# ViDieuKhienSTM32F103C8T6.net
KiCad netlist of a schematic drawn in Altium Designer
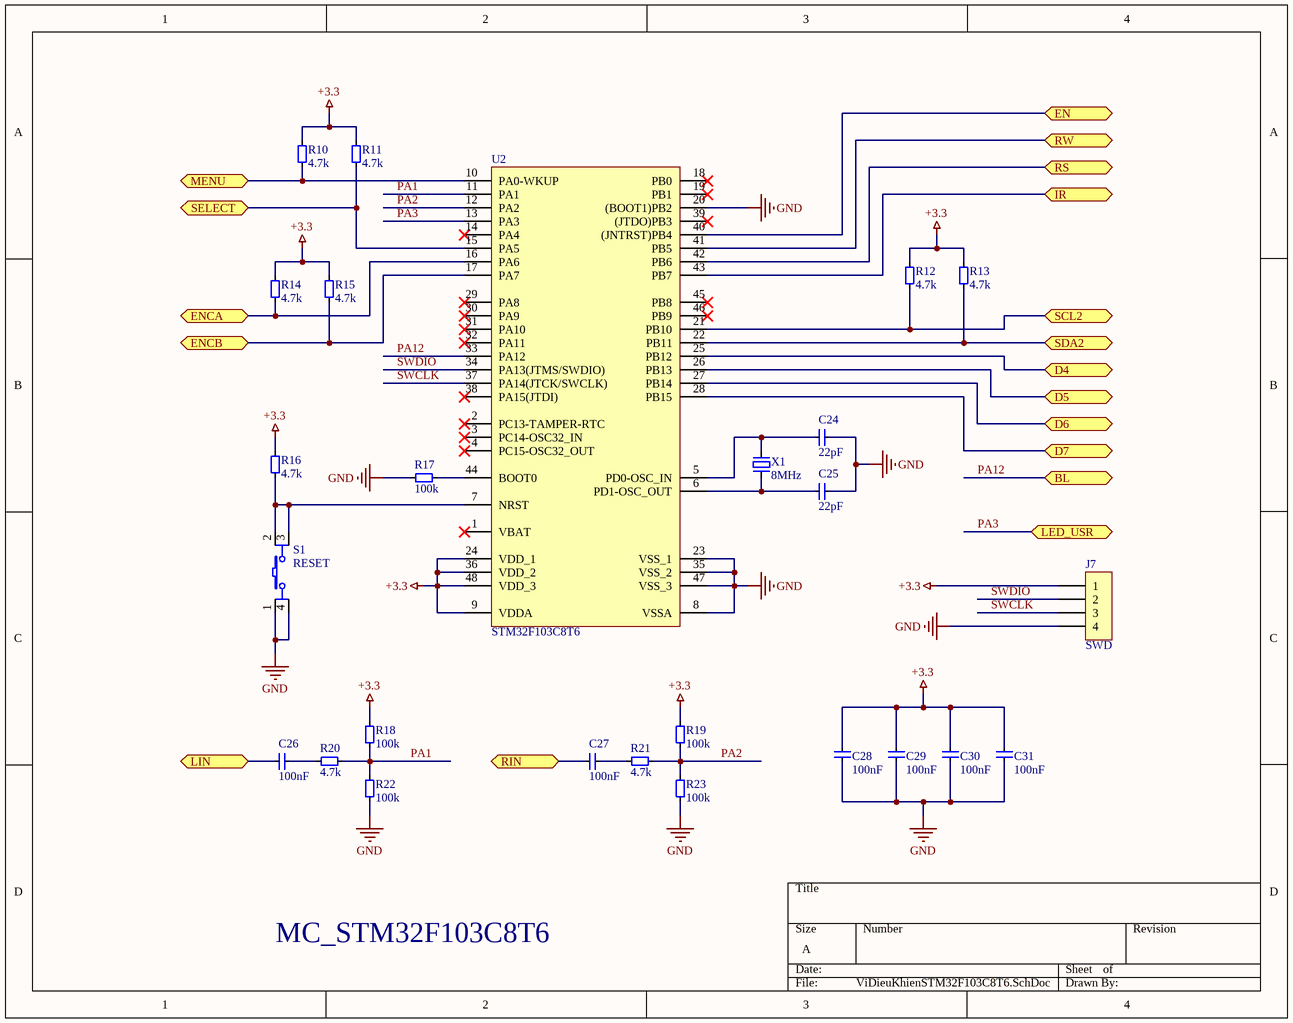
[diagram p0: ViDieuKhienSTM32F103C8T6.SchDoc]

(export (version "E")
  (design (tool "Eeschema 10.0.6"))
  (components
    (comp (ref "C24")
      (value "22pF")
      (footprint "C-0805")
      (description "Cac Loai Tu Khong Phan Cuc")
      (libsource (lib "phatvu1294_Lib") (part "CAP"))
    )
    (comp (ref "C25")
      (value "22pF")
      (footprint "C-0805")
      (description "Cac Loai Tu Khong Phan Cuc")
      (libsource (lib "phatvu1294_Lib") (part "CAP"))
    )
    (comp (ref "C26")
      (value "100nF")
      (footprint "C-0805")
      (description "Cac Loai Tu Khong Phan Cuc")
      (libsource (lib "phatvu1294_Lib") (part "CAP"))
    )
    (comp (ref "C27")
      (value "100nF")
      (footprint "C-0805")
      (description "Cac Loai Tu Khong Phan Cuc")
      (libsource (lib "phatvu1294_Lib") (part "CAP"))
    )
    (comp (ref "C28")
      (value "100nF")
      (footprint "C-0805")
      (description "Cac Loai Tu Khong Phan Cuc")
      (libsource (lib "phatvu1294_Lib") (part "CAP"))
    )
    (comp (ref "C29")
      (value "100nF")
      (footprint "C-0805")
      (description "Cac Loai Tu Khong Phan Cuc")
      (libsource (lib "phatvu1294_Lib") (part "CAP"))
    )
    (comp (ref "C30")
      (value "100nF")
      (footprint "C-0805")
      (description "Cac Loai Tu Khong Phan Cuc")
      (libsource (lib "phatvu1294_Lib") (part "CAP"))
    )
    (comp (ref "C31")
      (value "100nF")
      (footprint "C-0805")
      (description "Cac Loai Tu Khong Phan Cuc")
      (libsource (lib "phatvu1294_Lib") (part "CAP"))
    )
    (comp (ref "J7")
      (value "SWD")
      (footprint "JP1X4M-2.54")
      (description "Jump Don 4 Chan 2.54mm")
      (libsource (lib "phatvu1294_Lib") (part "JP1X4-2.54"))
    )
    (comp (ref "R10")
      (value "4.7k")
      (footprint "R-0805")
      (description "Cac Loai Dien Tro")
      (libsource (lib "phatvu1294_Lib") (part "RES"))
    )
    (comp (ref "R11")
      (value "4.7k")
      (footprint "R-0805")
      (description "Cac Loai Dien Tro")
      (libsource (lib "phatvu1294_Lib") (part "RES"))
    )
    (comp (ref "R12")
      (value "4.7k")
      (footprint "R-0805")
      (description "Cac Loai Dien Tro")
      (libsource (lib "phatvu1294_Lib") (part "RES"))
    )
    (comp (ref "R13")
      (value "4.7k")
      (footprint "R-0805")
      (description "Cac Loai Dien Tro")
      (libsource (lib "phatvu1294_Lib") (part "RES"))
    )
    (comp (ref "R14")
      (value "4.7k")
      (footprint "R-0805")
      (description "Cac Loai Dien Tro")
      (libsource (lib "phatvu1294_Lib") (part "RES"))
    )
    (comp (ref "R15")
      (value "4.7k")
      (footprint "R-0805")
      (description "Cac Loai Dien Tro")
      (libsource (lib "phatvu1294_Lib") (part "RES"))
    )
    (comp (ref "R16")
      (value "4.7k")
      (footprint "R-0805")
      (description "Cac Loai Dien Tro")
      (libsource (lib "phatvu1294_Lib") (part "RES"))
    )
    (comp (ref "R17")
      (value "100k")
      (footprint "R-0805")
      (description "Cac Loai Dien Tro")
      (libsource (lib "phatvu1294_Lib") (part "RES"))
    )
    (comp (ref "R18")
      (value "100k")
      (footprint "R-0805")
      (description "Cac Loai Dien Tro")
      (libsource (lib "phatvu1294_Lib") (part "RES"))
    )
    (comp (ref "R19")
      (value "100k")
      (footprint "R-0805")
      (description "Cac Loai Dien Tro")
      (libsource (lib "phatvu1294_Lib") (part "RES"))
    )
    (comp (ref "R20")
      (value "4.7k")
      (footprint "R-0805")
      (description "Cac Loai Dien Tro")
      (libsource (lib "phatvu1294_Lib") (part "RES"))
    )
    (comp (ref "R21")
      (value "4.7k")
      (footprint "R-0805")
      (description "Cac Loai Dien Tro")
      (libsource (lib "phatvu1294_Lib") (part "RES"))
    )
    (comp (ref "R22")
      (value "100k")
      (footprint "R-0805")
      (description "Cac Loai Dien Tro")
      (libsource (lib "phatvu1294_Lib") (part "RES"))
    )
    (comp (ref "R23")
      (value "100k")
      (footprint "R-0805")
      (description "Cac Loai Dien Tro")
      (libsource (lib "phatvu1294_Lib") (part "RES"))
    )
    (comp (ref "S1")
      (value "RESET")
      (footprint "SW4P-DIP-6X6MM")
      (description "Nut Nhan 4 Chan 6X6MM")
      (libsource (lib "phatvu1294_Lib") (part "SW4P-DIP-6X6MM"))
    )
    (comp (ref "U2")
      (value "STM32F103C8T6")
      (footprint "LQFP48-0.5-7X7MM")
      (description "VDK 32-Bit ARM Cortex-M3")
      (libsource (lib "phatvu1294_Lib") (part "STM32F103C8T6"))
    )
    (comp (ref "X1")
      (value "8MHz")
      (footprint "XTAL-HC49US")
      (description "Thach Anh 2 Chan HC49")
      (libsource (lib "phatvu1294_Lib") (part "XTAL-HC49"))
    )
  )
  (nets
    (net (code "1") (name "+3.3") (class "Default")
      (node (ref "C28") (pin "1") (pinfunction "1_1") (pintype "passive"))
      (node (ref "C29") (pin "1") (pinfunction "1_1") (pintype "passive"))
      (node (ref "C30") (pin "1") (pinfunction "1_1") (pintype "passive"))
      (node (ref "C31") (pin "1") (pinfunction "1_1") (pintype "passive"))
      (node (ref "J7") (pin "1") (pinfunction "1_1") (pintype "passive"))
      (node (ref "R10") (pin "2") (pinfunction "2_2") (pintype "passive"))
      (node (ref "R11") (pin "2") (pinfunction "2_2") (pintype "passive"))
      (node (ref "R12") (pin "2") (pinfunction "2_2") (pintype "passive"))
      (node (ref "R13") (pin "2") (pinfunction "2_2") (pintype "passive"))
      (node (ref "R14") (pin "2") (pinfunction "2_2") (pintype "passive"))
      (node (ref "R15") (pin "2") (pinfunction "2_2") (pintype "passive"))
      (node (ref "R16") (pin "2") (pinfunction "2_2") (pintype "passive"))
      (node (ref "R18") (pin "2") (pinfunction "2_2") (pintype "passive"))
      (node (ref "R19") (pin "2") (pinfunction "2_2") (pintype "passive"))
      (node (ref "U2") (pin "24") (pinfunction "VDD_1_24") (pintype "power_in"))
      (node (ref "U2") (pin "36") (pinfunction "VDD_2_36") (pintype "power_in"))
      (node (ref "U2") (pin "48") (pinfunction "VDD_3_48") (pintype "power_in"))
      (node (ref "U2") (pin "9") (pinfunction "VDDA_9") (pintype "power_in"))
    )
    (net (code "2") (name "/D4") (class "Default")
      (node (ref "U2") (pin "25") (pinfunction "PB12_25") (pintype "passive"))
    )
    (net (code "3") (name "/D5") (class "Default")
      (node (ref "U2") (pin "26") (pinfunction "PB13_26") (pintype "passive"))
    )
    (net (code "4") (name "/D6") (class "Default")
      (node (ref "U2") (pin "27") (pinfunction "PB14_27") (pintype "passive"))
    )
    (net (code "5") (name "/D7") (class "Default")
      (node (ref "U2") (pin "28") (pinfunction "PB15_28") (pintype "passive"))
    )
    (net (code "6") (name "/EN") (class "Default")
      (node (ref "U2") (pin "40") (pinfunction "(JNTRST)PB4_40") (pintype "passive"))
    )
    (net (code "7") (name "/ENCA") (class "Default")
      (node (ref "R14") (pin "1") (pinfunction "1_1") (pintype "passive"))
      (node (ref "U2") (pin "16") (pinfunction "PA6_16") (pintype "passive"))
    )
    (net (code "8") (name "/ENCB") (class "Default")
      (node (ref "R15") (pin "1") (pinfunction "1_1") (pintype "passive"))
      (node (ref "U2") (pin "17") (pinfunction "PA7_17") (pintype "passive"))
    )
    (net (code "9") (name "/IR") (class "Default")
      (node (ref "U2") (pin "43") (pinfunction "PB7_43") (pintype "passive"))
    )
    (net (code "10") (name "/LIN") (class "Default")
      (node (ref "C26") (pin "2") (pinfunction "2_2") (pintype "passive"))
    )
    (net (code "11") (name "/MENU") (class "Default")
      (node (ref "R10") (pin "1") (pinfunction "1_1") (pintype "passive"))
      (node (ref "U2") (pin "10") (pinfunction "PA0-WKUP_10") (pintype "passive"))
    )
    (net (code "12") (name "/PA1") (class "Default")
      (node (ref "R18") (pin "1") (pinfunction "1_1") (pintype "passive"))
      (node (ref "R20") (pin "1") (pinfunction "1_1") (pintype "passive"))
      (node (ref "R22") (pin "2") (pinfunction "2_2") (pintype "passive"))
      (node (ref "U2") (pin "11") (pinfunction "PA1_11") (pintype "passive"))
    )
    (net (code "13") (name "/PA2") (class "Default")
      (node (ref "R19") (pin "1") (pinfunction "1_1") (pintype "passive"))
      (node (ref "R21") (pin "1") (pinfunction "1_1") (pintype "passive"))
      (node (ref "R23") (pin "2") (pinfunction "2_2") (pintype "passive"))
      (node (ref "U2") (pin "12") (pinfunction "PA2_12") (pintype "passive"))
    )
    (net (code "14") (name "/PA3") (class "Default")
      (node (ref "U2") (pin "13") (pinfunction "PA3_13") (pintype "passive"))
    )
    (net (code "15") (name "/PA12") (class "Default")
      (node (ref "U2") (pin "33") (pinfunction "PA12_33") (pintype "passive"))
    )
    (net (code "16") (name "/RIN") (class "Default")
      (node (ref "C27") (pin "2") (pinfunction "2_2") (pintype "passive"))
    )
    (net (code "17") (name "/RS") (class "Default")
      (node (ref "U2") (pin "42") (pinfunction "PB6_42") (pintype "passive"))
    )
    (net (code "18") (name "/RW") (class "Default")
      (node (ref "U2") (pin "41") (pinfunction "PB5_41") (pintype "passive"))
    )
    (net (code "19") (name "/SCL2") (class "Default")
      (node (ref "R12") (pin "1") (pinfunction "1_1") (pintype "passive"))
      (node (ref "U2") (pin "21") (pinfunction "PB10_21") (pintype "passive"))
    )
    (net (code "20") (name "/SDA2") (class "Default")
      (node (ref "R13") (pin "1") (pinfunction "1_1") (pintype "passive"))
      (node (ref "U2") (pin "22") (pinfunction "PB11_22") (pintype "passive"))
    )
    (net (code "21") (name "/SELECT") (class "Default")
      (node (ref "R11") (pin "1") (pinfunction "1_1") (pintype "passive"))
      (node (ref "U2") (pin "15") (pinfunction "PA5_15") (pintype "passive"))
    )
    (net (code "22") (name "/SWCLK") (class "Default")
      (node (ref "J7") (pin "3") (pinfunction "3_3") (pintype "passive"))
      (node (ref "U2") (pin "37") (pinfunction "PA14(JTCK/SWCLK)_37") (pintype "passive"))
    )
    (net (code "23") (name "/SWDIO") (class "Default")
      (node (ref "J7") (pin "2") (pinfunction "2_2") (pintype "passive"))
      (node (ref "U2") (pin "34") (pinfunction "PA13(JTMS/SWDIO)_34") (pintype "passive"))
    )
    (net (code "24") (name "GND") (class "Default")
      (node (ref "C24") (pin "1") (pinfunction "1_1") (pintype "passive"))
      (node (ref "C25") (pin "1") (pinfunction "1_1") (pintype "passive"))
      (node (ref "C28") (pin "2") (pinfunction "2_2") (pintype "passive"))
      (node (ref "C29") (pin "2") (pinfunction "2_2") (pintype "passive"))
      (node (ref "C30") (pin "2") (pinfunction "2_2") (pintype "passive"))
      (node (ref "C31") (pin "2") (pinfunction "2_2") (pintype "passive"))
      (node (ref "J7") (pin "4") (pinfunction "4_4") (pintype "passive"))
      (node (ref "R17") (pin "1") (pinfunction "1_1") (pintype "passive"))
      (node (ref "R22") (pin "1") (pinfunction "1_1") (pintype "passive"))
      (node (ref "R23") (pin "1") (pinfunction "1_1") (pintype "passive"))
      (node (ref "S1") (pin "1") (pinfunction "1_1") (pintype "passive"))
      (node (ref "S1") (pin "4") (pinfunction "4_4") (pintype "passive"))
      (node (ref "U2") (pin "20") (pinfunction "(BOOT1)PB2_20") (pintype "passive"))
      (node (ref "U2") (pin "23") (pinfunction "VSS_1_23") (pintype "power_in"))
      (node (ref "U2") (pin "35") (pinfunction "VSS_2_35") (pintype "power_in"))
      (node (ref "U2") (pin "47") (pinfunction "VSS_3_47") (pintype "power_in"))
      (node (ref "U2") (pin "8") (pinfunction "VSSA_8") (pintype "power_in"))
    )
    (net (code "25") (name "Net-(C26-Pad1)") (class "Default")
      (node (ref "C26") (pin "1") (pinfunction "1_1") (pintype "passive"))
      (node (ref "R20") (pin "2") (pinfunction "2_2") (pintype "passive"))
    )
    (net (code "26") (name "Net-(C27-Pad1)") (class "Default")
      (node (ref "C27") (pin "1") (pinfunction "1_1") (pintype "passive"))
      (node (ref "R21") (pin "2") (pinfunction "2_2") (pintype "passive"))
    )
    (net (code "27") (name "Net-(U2-BOOT0)") (class "Default")
      (node (ref "R17") (pin "2") (pinfunction "2_2") (pintype "passive"))
      (node (ref "U2") (pin "44") (pinfunction "BOOT0_44") (pintype "passive"))
    )
    (net (code "28") (name "Net-(U2-NRST)") (class "Default")
      (node (ref "R16") (pin "1") (pinfunction "1_1") (pintype "passive"))
      (node (ref "S1") (pin "2") (pinfunction "2_2") (pintype "passive"))
      (node (ref "S1") (pin "3") (pinfunction "3_3") (pintype "passive"))
      (node (ref "U2") (pin "7") (pinfunction "NRST_7") (pintype "passive"))
    )
    (net (code "29") (name "Net-(U2-PD0-OSC_IN)") (class "Default")
      (node (ref "C24") (pin "2") (pinfunction "2_2") (pintype "passive"))
      (node (ref "U2") (pin "5") (pinfunction "PD0-OSC_IN_5") (pintype "passive"))
      (node (ref "X1") (pin "1") (pinfunction "1_1") (pintype "passive"))
    )
    (net (code "30") (name "Net-(U2-PD1-OSC_OUT)") (class "Default")
      (node (ref "C25") (pin "2") (pinfunction "2_2") (pintype "passive"))
      (node (ref "U2") (pin "6") (pinfunction "PD1-OSC_OUT_6") (pintype "passive"))
      (node (ref "X1") (pin "2") (pinfunction "2_2") (pintype "passive"))
    )
    (net (code "31") (name "unconnected-(U2-(JTDO)PB3-Pad39)") (class "Default")
      (node (ref "U2") (pin "39") (pinfunction "(JTDO)PB3_39") (pintype "passive+no_connect"))
    )
    (net (code "32") (name "unconnected-(U2-PA4-Pad14)") (class "Default")
      (node (ref "U2") (pin "14") (pinfunction "PA4_14") (pintype "passive+no_connect"))
    )
    (net (code "33") (name "unconnected-(U2-PA8-Pad29)") (class "Default")
      (node (ref "U2") (pin "29") (pinfunction "PA8_29") (pintype "passive+no_connect"))
    )
    (net (code "34") (name "unconnected-(U2-PA9-Pad30)") (class "Default")
      (node (ref "U2") (pin "30") (pinfunction "PA9_30") (pintype "passive+no_connect"))
    )
    (net (code "35") (name "unconnected-(U2-PA10-Pad31)") (class "Default")
      (node (ref "U2") (pin "31") (pinfunction "PA10_31") (pintype "passive+no_connect"))
    )
    (net (code "36") (name "unconnected-(U2-PA11-Pad32)") (class "Default")
      (node (ref "U2") (pin "32") (pinfunction "PA11_32") (pintype "passive+no_connect"))
    )
    (net (code "37") (name "unconnected-(U2-PA15(JTDI)-Pad38)") (class "Default")
      (node (ref "U2") (pin "38") (pinfunction "PA15(JTDI)_38") (pintype "passive+no_connect"))
    )
    (net (code "38") (name "unconnected-(U2-PB0-Pad18)") (class "Default")
      (node (ref "U2") (pin "18") (pinfunction "PB0_18") (pintype "passive+no_connect"))
    )
    (net (code "39") (name "unconnected-(U2-PB1-Pad19)") (class "Default")
      (node (ref "U2") (pin "19") (pinfunction "PB1_19") (pintype "passive+no_connect"))
    )
    (net (code "40") (name "unconnected-(U2-PB8-Pad45)") (class "Default")
      (node (ref "U2") (pin "45") (pinfunction "PB8_45") (pintype "passive+no_connect"))
    )
    (net (code "41") (name "unconnected-(U2-PB9-Pad46)") (class "Default")
      (node (ref "U2") (pin "46") (pinfunction "PB9_46") (pintype "passive+no_connect"))
    )
    (net (code "42") (name "unconnected-(U2-PC13-TAMPER-RTC-Pad2)") (class "Default")
      (node (ref "U2") (pin "2") (pinfunction "PC13-TAMPER-RTC_2") (pintype "passive+no_connect"))
    )
    (net (code "43") (name "unconnected-(U2-PC14-OSC32_IN-Pad3)") (class "Default")
      (node (ref "U2") (pin "3") (pinfunction "PC14-OSC32_IN_3") (pintype "passive+no_connect"))
    )
    (net (code "44") (name "unconnected-(U2-PC15-OSC32_OUT-Pad4)") (class "Default")
      (node (ref "U2") (pin "4") (pinfunction "PC15-OSC32_OUT_4") (pintype "passive+no_connect"))
    )
    (net (code "45") (name "unconnected-(U2-VBAT-Pad1)") (class "Default")
      (node (ref "U2") (pin "1") (pinfunction "VBAT_1") (pintype "power_in+no_connect"))
    )
  )
)
